# Papa_Soundie.net
KiCad netlist of a schematic drawn in EAGLE
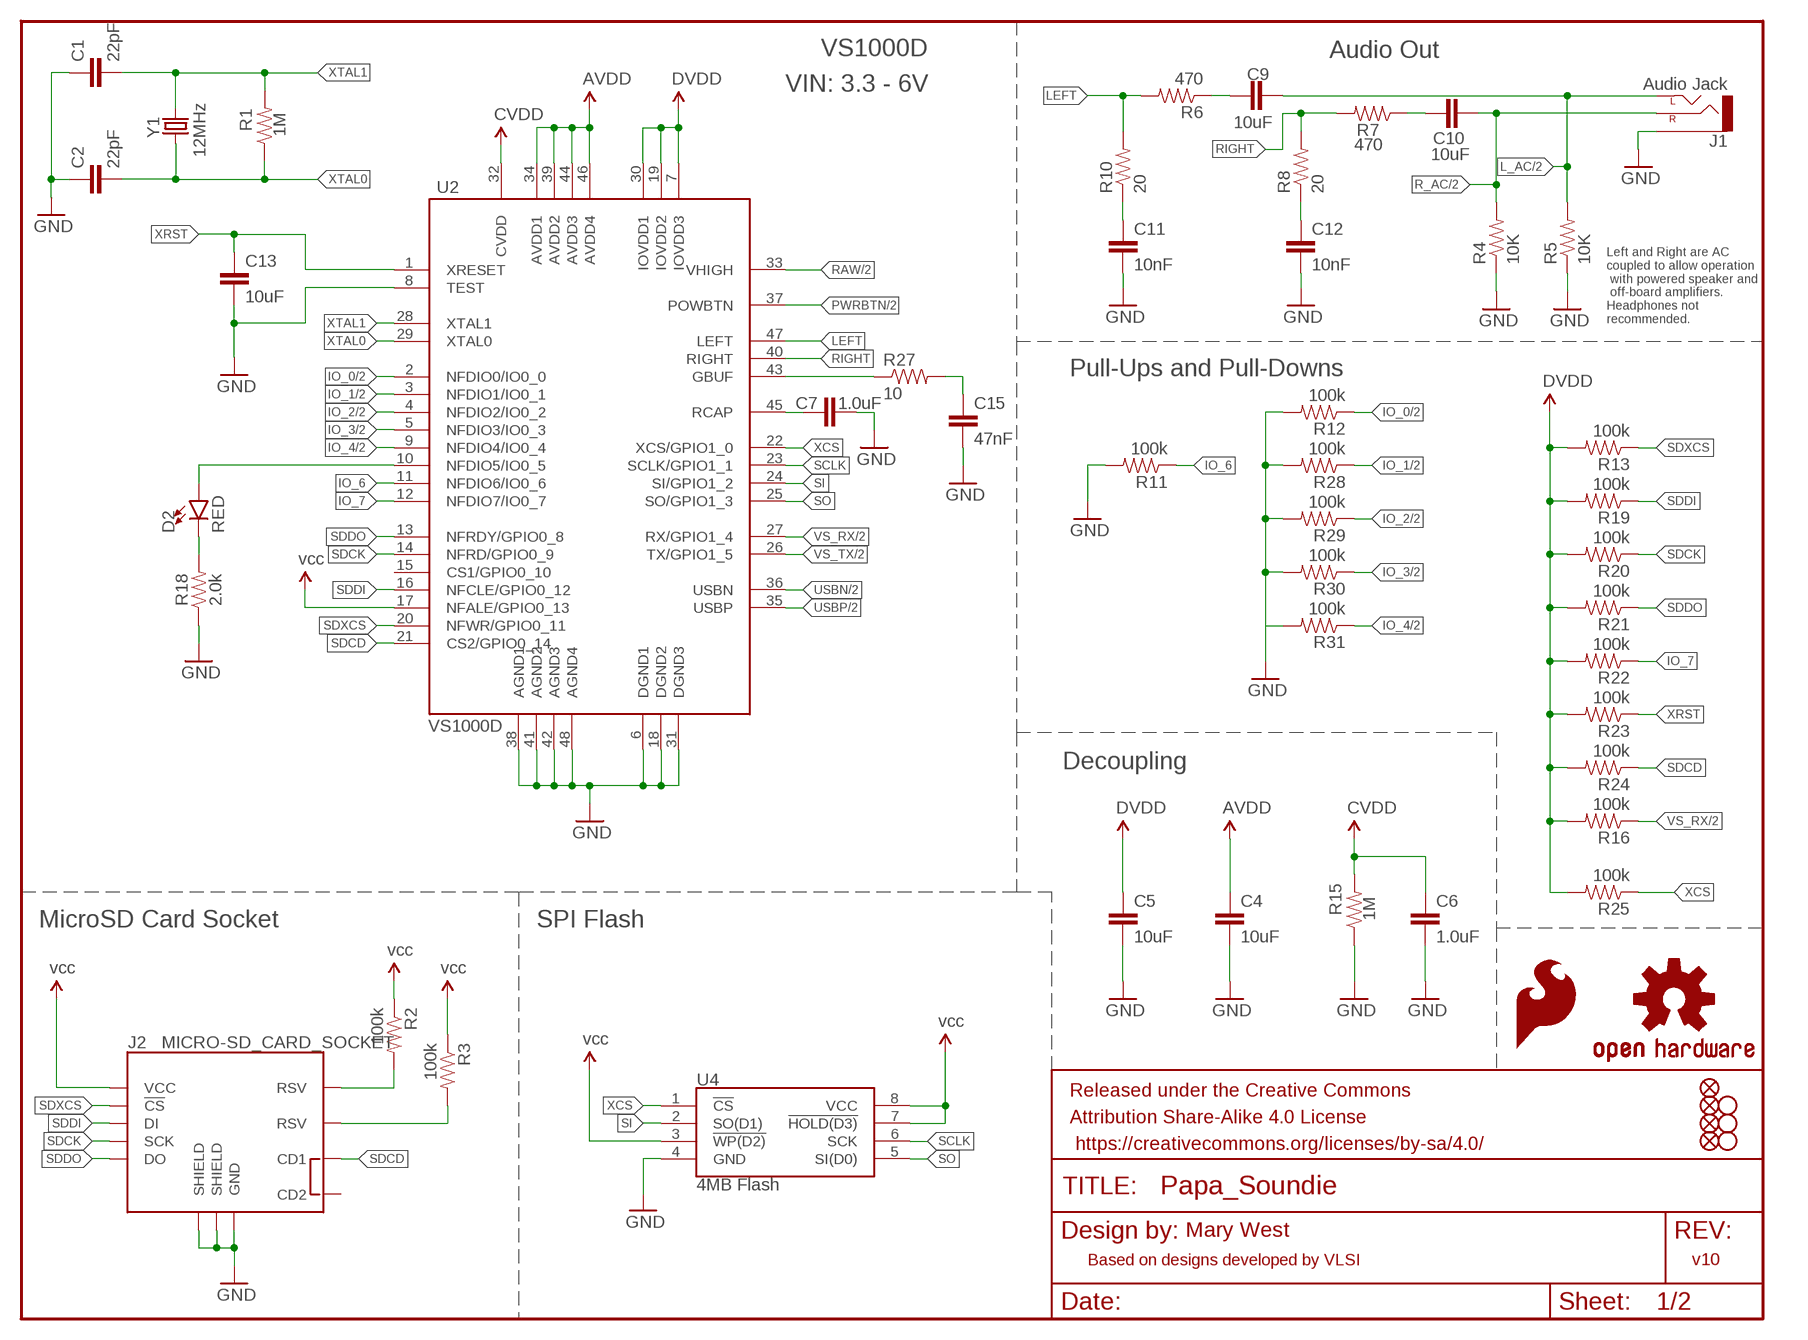
[diagram p0: schematic, sheet 1]
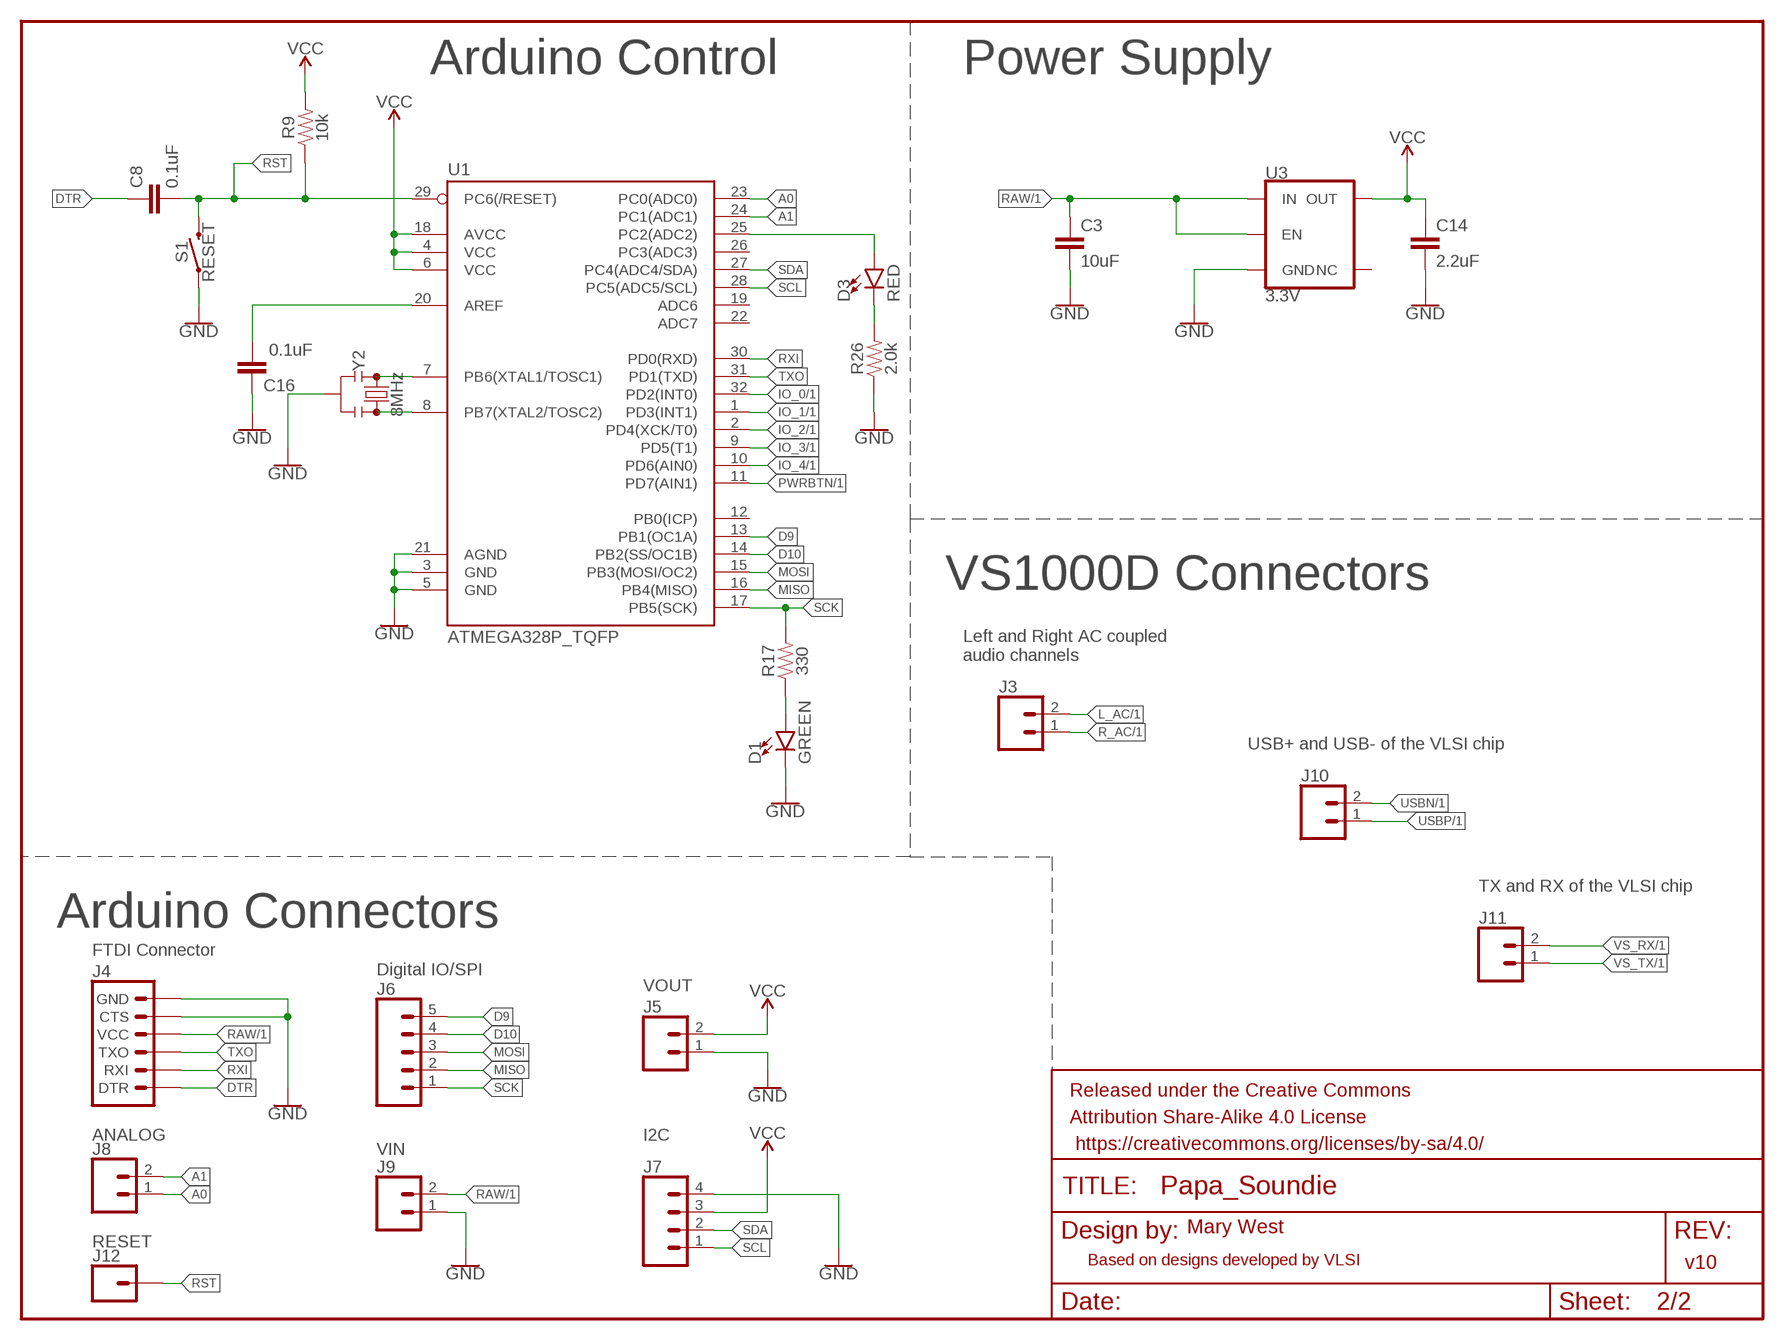
[diagram p1: schematic, sheet 2]

(export (version "E")
  (design (tool "Eeschema 10.0.6"))
  (components
    (comp (ref "C3")
      (value "10uF")
      (footprint "eagle-import:0603")
      (libsource (lib "eagle-import") (part "10UF-0603-6.3V-20%"))
    )
    (comp (ref "C8")
      (value "0.1uF")
      (footprint "eagle-import:0603")
      (libsource (lib "eagle-import") (part "0.1UF-0603-25V-(+80/-20%)"))
    )
    (comp (ref "C14")
      (value "2.2uF")
      (footprint "eagle-import:0603")
      (libsource (lib "eagle-import") (part "2.2UF-0603-10V-20%"))
    )
    (comp (ref "C16")
      (value "0.1uF")
      (footprint "eagle-import:0603")
      (libsource (lib "eagle-import") (part "0.1UF-0603-25V-(+80/-20%)"))
    )
    (comp (ref "D1")
      (value "GREEN")
      (footprint "eagle-import:LED-0603")
      (libsource (lib "eagle-import") (part "LED-GREEN0603"))
    )
    (comp (ref "D3")
      (value "RED")
      (footprint "eagle-import:LED-0603")
      (libsource (lib "eagle-import") (part "LED-RED0603"))
    )
    (comp (ref "FRAME2")
      (value "FRAME-LETTER")
      (footprint "eagle-import:CREATIVE_COMMONS")
      (libsource (lib "eagle-import") (part "FRAME-LETTER"))
    )
    (comp (ref "J3")
      (value "CONN_02")
      (footprint "eagle-import:1X02")
      (libsource (lib "eagle-import") (part "CONN_02"))
    )
    (comp (ref "J4")
      (value "6_PIN_SERIAL_TARGETSILK")
      (footprint "eagle-import:6_PIN_SERIAL_TARGET_SIDE_W_SILK")
      (libsource (lib "eagle-import") (part "6_PIN_SERIAL_TARGETSILK"))
    )
    (comp (ref "J5")
      (value "CONN_02")
      (footprint "eagle-import:1X02")
      (libsource (lib "eagle-import") (part "CONN_02"))
    )
    (comp (ref "J6")
      (value "CONN_05")
      (footprint "eagle-import:1X05")
      (libsource (lib "eagle-import") (part "CONN_05"))
    )
    (comp (ref "J7")
      (value "CONN_04")
      (footprint "eagle-import:1X04")
      (libsource (lib "eagle-import") (part "CONN_04"))
    )
    (comp (ref "J8")
      (value "CONN_02")
      (footprint "eagle-import:1X02")
      (libsource (lib "eagle-import") (part "CONN_02"))
    )
    (comp (ref "J9")
      (value "CONN_02")
      (footprint "eagle-import:1X02")
      (libsource (lib "eagle-import") (part "CONN_02"))
    )
    (comp (ref "J10")
      (value "CONN_02")
      (footprint "eagle-import:1X02")
      (libsource (lib "eagle-import") (part "CONN_02"))
    )
    (comp (ref "J11")
      (value "CONN_02")
      (footprint "eagle-import:1X02")
      (libsource (lib "eagle-import") (part "CONN_02"))
    )
    (comp (ref "J12")
      (value "CONN_01")
      (footprint "eagle-import:1X01")
      (libsource (lib "eagle-import") (part "CONN_01"))
    )
    (comp (ref "R9")
      (value "10k")
      (footprint "eagle-import:0603")
      (libsource (lib "eagle-import") (part "10KOHM-0603-1/10W-1%"))
    )
    (comp (ref "R17")
      (value "330")
      (footprint "eagle-import:0603")
      (libsource (lib "eagle-import") (part "330OHM-0603-1/10W-1%"))
    )
    (comp (ref "R26")
      (value "2.0k")
      (footprint "eagle-import:0603")
      (libsource (lib "eagle-import") (part "2.0KOHM-0603-1/10W-5%"))
    )
    (comp (ref "S1")
      (value "RESET")
      (footprint "eagle-import:TACTILE_SWITCH_SMD_5.2MM")
      (libsource (lib "eagle-import") (part "MOMENTARY-SWITCH-SPST-SMD-5.2MM"))
    )
    (comp (ref "U1")
      (value "ATMEGA328P_TQFP")
      (footprint "eagle-import:TQFP32-08")
      (libsource (lib "eagle-import") (part "ATMEGA328P_TQFP"))
    )
    (comp (ref "U3")
      (value "3.3V")
      (footprint "eagle-import:SOT23-5")
      (libsource (lib "eagle-import") (part "V_REG_AP2112K-3.3V"))
    )
    (comp (ref "Y2")
      (value "8MHz")
      (footprint "eagle-import:RESONATOR-SMD-3.2X1.3")
      (libsource (lib "eagle-import") (part "RESONATOR-8MHZSMD_3.2X1.3"))
    )
    (comp (ref "C1")
      (value "22pF")
      (footprint "eagle-import:0603-CAP")
      (libsource (lib "eagle-import") (part "22PF-50V-5%(0603)"))
    )
    (comp (ref "C2")
      (value "22pF")
      (footprint "eagle-import:0603-CAP")
      (libsource (lib "eagle-import") (part "22PF-50V-5%(0603)"))
    )
    (comp (ref "C4")
      (value "10uF")
      (footprint "eagle-import:0603")
      (libsource (lib "eagle-import") (part "10UF-0603-6.3V-20%"))
    )
    (comp (ref "C5")
      (value "10uF")
      (footprint "eagle-import:0603")
      (libsource (lib "eagle-import") (part "10UF-0603-6.3V-20%"))
    )
    (comp (ref "C6")
      (value "1.0uF")
      (footprint "eagle-import:0603-CAP")
      (libsource (lib "eagle-import") (part "1.0UF-16V-10%(0603)"))
    )
    (comp (ref "C7")
      (value "1.0uF")
      (footprint "eagle-import:0603-CAP")
      (libsource (lib "eagle-import") (part "1.0UF-16V-10%(0603)"))
    )
    (comp (ref "C9")
      (value "10uF")
      (footprint "eagle-import:0603-CAP")
      (libsource (lib "eagle-import") (part "10UF-6.3V-20%(0603)"))
    )
    (comp (ref "C10")
      (value "10uF")
      (footprint "eagle-import:0603-CAP")
      (libsource (lib "eagle-import") (part "10UF-6.3V-20%(0603)"))
    )
    (comp (ref "C11")
      (value "10nF")
      (footprint "eagle-import:0603-CAP")
      (libsource (lib "eagle-import") (part "10NF/10000PF-50V-10%(0603)"))
    )
    (comp (ref "C12")
      (value "10nF")
      (footprint "eagle-import:0603-CAP")
      (libsource (lib "eagle-import") (part "10NF/10000PF-50V-10%(0603)"))
    )
    (comp (ref "C13")
      (value "10uF")
      (footprint "eagle-import:0603-CAP")
      (libsource (lib "eagle-import") (part "10UF-6.3V-20%(0603)"))
    )
    (comp (ref "C15")
      (value "47nF")
      (footprint "eagle-import:0603-CAP")
      (libsource (lib "eagle-import") (part "47NF(0.047UF/47000PF)-25V-5%(0603)SMD"))
    )
    (comp (ref "D2")
      (value "RED")
      (footprint "eagle-import:LED-0603")
      (libsource (lib "eagle-import") (part "LED-RED0603"))
    )
    (comp (ref "FD1")
      (value "FIDUCIALUFIDUCIAL")
      (footprint "eagle-import:FIDUCIAL-MICRO")
      (libsource (lib "eagle-import") (part "FIDUCIALUFIDUCIAL"))
    )
    (comp (ref "FD2")
      (value "FIDUCIALUFIDUCIAL")
      (footprint "eagle-import:FIDUCIAL-MICRO")
      (libsource (lib "eagle-import") (part "FIDUCIALUFIDUCIAL"))
    )
    (comp (ref "FD3")
      (value "FIDUCIALUFIDUCIAL")
      (footprint "eagle-import:FIDUCIAL-MICRO")
      (libsource (lib "eagle-import") (part "FIDUCIALUFIDUCIAL"))
    )
    (comp (ref "FD4")
      (value "FIDUCIALUFIDUCIAL")
      (footprint "eagle-import:FIDUCIAL-MICRO")
      (libsource (lib "eagle-import") (part "FIDUCIALUFIDUCIAL"))
    )
    (comp (ref "FRAME1")
      (value "FRAME-LETTER")
      (footprint "eagle-import:CREATIVE_COMMONS")
      (libsource (lib "eagle-import") (part "FRAME-LETTER"))
    )
    (comp (ref "H1")
      (value "STAND-OFFTIGHT")
      (footprint "eagle-import:STAND-OFF-TIGHT")
      (libsource (lib "eagle-import") (part "STAND-OFFTIGHT"))
    )
    (comp (ref "H2")
      (value "STAND-OFFTIGHT")
      (footprint "eagle-import:STAND-OFF-TIGHT")
      (libsource (lib "eagle-import") (part "STAND-OFFTIGHT"))
    )
    (comp (ref "H3")
      (value "STAND-OFFTIGHT")
      (footprint "eagle-import:STAND-OFF-TIGHT")
      (libsource (lib "eagle-import") (part "STAND-OFFTIGHT"))
    )
    (comp (ref "J1")
      (value "Audio Jack")
      (footprint "eagle-import:AUDIO-JACK-3.5MM-SMD")
      (libsource (lib "eagle-import") (part "AUDIO-JACKSMD2"))
    )
    (comp (ref "J2")
      (value "MICRO-SD_CARD_SOCKET")
      (footprint "eagle-import:MICRO-SD-SOCKET")
      (libsource (lib "eagle-import") (part "MICRO-SD_CARD_SOCKET"))
    )
    (comp (ref "LOGO1")
      (value "OSHW-LOGOL")
      (footprint "eagle-import:OSHW-LOGO-L")
      (libsource (lib "eagle-import") (part "OSHW-LOGOL"))
    )
    (comp (ref "LOGO2")
      (value "SFE_LOGO_FLAME.2_INCH")
      (footprint "eagle-import:SFE_LOGO_FLAME_.2")
      (libsource (lib "eagle-import") (part "SFE_LOGO_FLAME.2_INCH"))
    )
    (comp (ref "R1")
      (value "1M")
      (footprint "eagle-import:0603-RES")
      (libsource (lib "eagle-import") (part "1MOHM-1/10W-1%(0603)"))
    )
    (comp (ref "R2")
      (value "100k")
      (footprint "eagle-import:0603-RES")
      (libsource (lib "eagle-import") (part "100KOHM-1/10W-1%(0603)"))
    )
    (comp (ref "R3")
      (value "100k")
      (footprint "eagle-import:0603-RES")
      (libsource (lib "eagle-import") (part "100KOHM-1/10W-1%(0603)"))
    )
    (comp (ref "R4")
      (value "10K")
      (footprint "eagle-import:0603-RES")
      (libsource (lib "eagle-import") (part "10KOHM-1/10W-1%(0603)0603"))
    )
    (comp (ref "R5")
      (value "10K")
      (footprint "eagle-import:0603-RES")
      (libsource (lib "eagle-import") (part "10KOHM-1/10W-1%(0603)0603"))
    )
    (comp (ref "R6")
      (value "470")
      (footprint "eagle-import:0603-RES")
      (libsource (lib "eagle-import") (part "470OHM1/10W1%(0603)"))
    )
    (comp (ref "R7")
      (value "470")
      (footprint "eagle-import:0603-RES")
      (libsource (lib "eagle-import") (part "470OHM1/10W1%(0603)"))
    )
    (comp (ref "R8")
      (value "20")
      (footprint "eagle-import:0603-RES")
      (libsource (lib "eagle-import") (part "20OHM1/10W1%(0603)SMD"))
    )
    (comp (ref "R10")
      (value "20")
      (footprint "eagle-import:0603-RES")
      (libsource (lib "eagle-import") (part "20OHM1/10W1%(0603)SMD"))
    )
    (comp (ref "R11")
      (value "100k")
      (footprint "eagle-import:0603-RES")
      (libsource (lib "eagle-import") (part "100KOHM-1/10W-1%(0603)"))
    )
    (comp (ref "R12")
      (value "100k")
      (footprint "eagle-import:0603-RES")
      (libsource (lib "eagle-import") (part "100KOHM-1/10W-1%(0603)"))
    )
    (comp (ref "R13")
      (value "100k")
      (footprint "eagle-import:0603-RES")
      (libsource (lib "eagle-import") (part "100KOHM-1/10W-1%(0603)"))
    )
    (comp (ref "R15")
      (value "1M")
      (footprint "eagle-import:0603-RES")
      (libsource (lib "eagle-import") (part "1MOHM-1/10W-1%(0603)"))
    )
    (comp (ref "R16")
      (value "100k")
      (footprint "eagle-import:0603-RES")
      (libsource (lib "eagle-import") (part "100KOHM-1/10W-1%(0603)"))
    )
    (comp (ref "R18")
      (value "2.0k")
      (footprint "eagle-import:0603")
      (libsource (lib "eagle-import") (part "2.0KOHM-0603-1/10W-5%"))
    )
    (comp (ref "R19")
      (value "100k")
      (footprint "eagle-import:0603-RES")
      (libsource (lib "eagle-import") (part "100KOHM-1/10W-1%(0603)"))
    )
    (comp (ref "R20")
      (value "100k")
      (footprint "eagle-import:0603-RES")
      (libsource (lib "eagle-import") (part "100KOHM-1/10W-1%(0603)"))
    )
    (comp (ref "R21")
      (value "100k")
      (footprint "eagle-import:0603-RES")
      (libsource (lib "eagle-import") (part "100KOHM-1/10W-1%(0603)"))
    )
    (comp (ref "R22")
      (value "100k")
      (footprint "eagle-import:0603-RES")
      (libsource (lib "eagle-import") (part "100KOHM-1/10W-1%(0603)"))
    )
    (comp (ref "R23")
      (value "100k")
      (footprint "eagle-import:0603-RES")
      (libsource (lib "eagle-import") (part "100KOHM-1/10W-1%(0603)"))
    )
    (comp (ref "R24")
      (value "100k")
      (footprint "eagle-import:0603-RES")
      (libsource (lib "eagle-import") (part "100KOHM-1/10W-1%(0603)"))
    )
    (comp (ref "R25")
      (value "100k")
      (footprint "eagle-import:0603-RES")
      (libsource (lib "eagle-import") (part "100KOHM-1/10W-1%(0603)"))
    )
    (comp (ref "R27")
      (value "10")
      (footprint "eagle-import:0603-RES")
      (libsource (lib "eagle-import") (part "10OHM-1/10W-5%0603SMD"))
    )
    (comp (ref "R28")
      (value "100k")
      (footprint "eagle-import:0603-RES")
      (libsource (lib "eagle-import") (part "100KOHM-1/10W-1%(0603)"))
    )
    (comp (ref "R29")
      (value "100k")
      (footprint "eagle-import:0603-RES")
      (libsource (lib "eagle-import") (part "100KOHM-1/10W-1%(0603)"))
    )
    (comp (ref "R30")
      (value "100k")
      (footprint "eagle-import:0603-RES")
      (libsource (lib "eagle-import") (part "100KOHM-1/10W-1%(0603)"))
    )
    (comp (ref "R31")
      (value "100k")
      (footprint "eagle-import:0603-RES")
      (libsource (lib "eagle-import") (part "100KOHM-1/10W-1%(0603)"))
    )
    (comp (ref "U2")
      (value "VS1000D")
      (footprint "eagle-import:LQFP-48")
      (fields (field (name "PROD_ID") "LPA-12743"))
      (libsource (lib "eagle-import") (part "VS1000"))
    )
    (comp (ref "U4")
      (value "4MB Flash")
      (footprint "eagle-import:SO08")
      (libsource (lib "eagle-import") (part "AT25SF041"))
    )
    (comp (ref "Y1")
      (value "12MHz")
      (footprint "eagle-import:CRYSTAL-SMD-5X3")
      (libsource (lib "eagle-import") (part "CRYSTALCRYSTAL-SMD-5X3-12MHZ"))
    )
  )
  (nets
    (net (code "1") (name "A0") (class "Default")
      (node (ref "J8") (pin "1") (pinfunction "1_1") (pintype "passive"))
      (node (ref "U1") (pin "23") (pinfunction "PC0(ADC0)_23") (pintype "bidirectional"))
    )
    (net (code "2") (name "A1") (class "Default")
      (node (ref "J8") (pin "2") (pinfunction "2_2") (pintype "passive"))
      (node (ref "U1") (pin "24") (pinfunction "PC1(ADC1)_24") (pintype "bidirectional"))
    )
    (net (code "3") (name "AVDD") (class "Default")
      (node (ref "C4") (pin "1") (pinfunction "1_1") (pintype "passive"))
      (node (ref "U2") (pin "34") (pinfunction "AVDD1_34") (pintype "bidirectional"))
      (node (ref "U2") (pin "39") (pinfunction "AVDD2_39") (pintype "bidirectional"))
      (node (ref "U2") (pin "44") (pinfunction "AVDD3_44") (pintype "bidirectional"))
      (node (ref "U2") (pin "46") (pinfunction "AVDD4_46") (pintype "bidirectional"))
    )
    (net (code "4") (name "CVDD") (class "Default")
      (node (ref "C6") (pin "1") (pinfunction "1_1") (pintype "passive"))
      (node (ref "R15") (pin "2") (pinfunction "2_2") (pintype "passive"))
      (node (ref "U2") (pin "32") (pinfunction "CVDD_32") (pintype "bidirectional"))
    )
    (net (code "5") (name "D9") (class "Default")
      (node (ref "J6") (pin "5") (pinfunction "5_5") (pintype "passive"))
      (node (ref "U1") (pin "13") (pinfunction "PB1(OC1A)_13") (pintype "bidirectional"))
    )
    (net (code "6") (name "D10") (class "Default")
      (node (ref "J6") (pin "4") (pinfunction "4_4") (pintype "passive"))
      (node (ref "U1") (pin "14") (pinfunction "PB2(SS/OC1B)_14") (pintype "bidirectional"))
    )
    (net (code "7") (name "DTR") (class "Default")
      (node (ref "C8") (pin "1") (pinfunction "1_1") (pintype "passive"))
      (node (ref "J4") (pin "P$1") (pinfunction "DTR_P$1") (pintype "passive"))
    )
    (net (code "8") (name "DVDD") (class "Default")
      (node (ref "C5") (pin "1") (pinfunction "1_1") (pintype "passive"))
      (node (ref "R13") (pin "2") (pinfunction "2_2") (pintype "passive"))
      (node (ref "R16") (pin "2") (pinfunction "2_2") (pintype "passive"))
      (node (ref "R19") (pin "2") (pinfunction "2_2") (pintype "passive"))
      (node (ref "R20") (pin "2") (pinfunction "2_2") (pintype "passive"))
      (node (ref "R21") (pin "2") (pinfunction "2_2") (pintype "passive"))
      (node (ref "R22") (pin "2") (pinfunction "2_2") (pintype "passive"))
      (node (ref "R23") (pin "2") (pinfunction "2_2") (pintype "passive"))
      (node (ref "R24") (pin "2") (pinfunction "2_2") (pintype "passive"))
      (node (ref "R25") (pin "2") (pinfunction "2_2") (pintype "passive"))
      (node (ref "U2") (pin "19") (pinfunction "IOVDD2_19") (pintype "bidirectional"))
      (node (ref "U2") (pin "30") (pinfunction "IOVDD1_30") (pintype "bidirectional"))
      (node (ref "U2") (pin "7") (pinfunction "IOVDD3_7") (pintype "bidirectional"))
    )
    (net (code "9") (name "GND") (class "Default")
      (node (ref "C1") (pin "1") (pinfunction "1_1") (pintype "passive"))
      (node (ref "C11") (pin "2") (pinfunction "2_2") (pintype "passive"))
      (node (ref "C12") (pin "2") (pinfunction "2_2") (pintype "passive"))
      (node (ref "C13") (pin "2") (pinfunction "2_2") (pintype "passive"))
      (node (ref "C14") (pin "2") (pinfunction "2_2") (pintype "passive"))
      (node (ref "C15") (pin "2") (pinfunction "2_2") (pintype "passive"))
      (node (ref "C16") (pin "1") (pinfunction "1_1") (pintype "passive"))
      (node (ref "C2") (pin "1") (pinfunction "1_1") (pintype "passive"))
      (node (ref "C3") (pin "2") (pinfunction "2_2") (pintype "passive"))
      (node (ref "C4") (pin "2") (pinfunction "2_2") (pintype "passive"))
      (node (ref "C5") (pin "2") (pinfunction "2_2") (pintype "passive"))
      (node (ref "C6") (pin "2") (pinfunction "2_2") (pintype "passive"))
      (node (ref "C7") (pin "2") (pinfunction "2_2") (pintype "passive"))
      (node (ref "D1") (pin "C") (pinfunction "C_C") (pintype "passive"))
      (node (ref "J1") (pin "SLEEVE") (pinfunction "SLEEVE_SLEEVE") (pintype "bidirectional"))
      (node (ref "J2") (pin "GND") (pinfunction "GND_GND") (pintype "bidirectional"))
      (node (ref "J2") (pin "GND1") (pinfunction "SHIELD_GND1") (pintype "bidirectional"))
      (node (ref "J2") (pin "GND3") (pinfunction "SHIELD_GND3") (pintype "bidirectional"))
      (node (ref "J4") (pin "P$5") (pinfunction "CTS_P$5") (pintype "passive"))
      (node (ref "J4") (pin "P$6") (pinfunction "GND_P$6") (pintype "passive"))
      (node (ref "J5") (pin "1") (pinfunction "1_1") (pintype "passive"))
      (node (ref "J7") (pin "4") (pinfunction "4_4") (pintype "passive"))
      (node (ref "J9") (pin "1") (pinfunction "1_1") (pintype "passive"))
      (node (ref "R11") (pin "2") (pinfunction "2_2") (pintype "passive"))
      (node (ref "R12") (pin "2") (pinfunction "2_2") (pintype "passive"))
      (node (ref "R15") (pin "1") (pinfunction "1_1") (pintype "passive"))
      (node (ref "R18") (pin "1") (pinfunction "1_1") (pintype "passive"))
      (node (ref "R26") (pin "1") (pinfunction "1_1") (pintype "passive"))
      (node (ref "R28") (pin "2") (pinfunction "2_2") (pintype "passive"))
      (node (ref "R29") (pin "2") (pinfunction "2_2") (pintype "passive"))
      (node (ref "R30") (pin "2") (pinfunction "2_2") (pintype "passive"))
      (node (ref "R31") (pin "2") (pinfunction "2_2") (pintype "passive"))
      (node (ref "R4") (pin "1") (pinfunction "1_1") (pintype "passive"))
      (node (ref "R5") (pin "1") (pinfunction "1_1") (pintype "passive"))
      (node (ref "S1") (pin "1") (pinfunction "1_1") (pintype "passive"))
      (node (ref "U1") (pin "21") (pinfunction "AGND_21") (pintype "bidirectional"))
      (node (ref "U1") (pin "3") (pinfunction "GND_3") (pintype "bidirectional"))
      (node (ref "U1") (pin "5") (pinfunction "GND_5") (pintype "bidirectional"))
      (node (ref "U2") (pin "18") (pinfunction "DGND2_18") (pintype "bidirectional"))
      (node (ref "U2") (pin "31") (pinfunction "DGND3_31") (pintype "bidirectional"))
      (node (ref "U2") (pin "38") (pinfunction "AGND1_38") (pintype "bidirectional"))
      (node (ref "U2") (pin "41") (pinfunction "AGND2_41") (pintype "bidirectional"))
      (node (ref "U2") (pin "42") (pinfunction "AGND3_42") (pintype "bidirectional"))
      (node (ref "U2") (pin "48") (pinfunction "AGND4_48") (pintype "bidirectional"))
      (node (ref "U2") (pin "6") (pinfunction "DGND1_6") (pintype "bidirectional"))
      (node (ref "U2") (pin "8") (pinfunction "TEST_8") (pintype "bidirectional"))
      (node (ref "U3") (pin "2") (pinfunction "GND_2") (pintype "input"))
      (node (ref "U4") (pin "4") (pinfunction "GND_4") (pintype "bidirectional"))
      (node (ref "Y2") (pin "2") (pinfunction "2_2") (pintype "passive"))
    )
    (net (code "10") (name "IO_0") (class "Default")
      (node (ref "R12") (pin "1") (pinfunction "1_1") (pintype "passive"))
      (node (ref "U1") (pin "32") (pinfunction "PD2(INT0)_32") (pintype "bidirectional"))
      (node (ref "U2") (pin "2") (pinfunction "NFDIO0/IO0_0_2") (pintype "bidirectional"))
    )
    (net (code "11") (name "IO_1") (class "Default")
      (node (ref "R28") (pin "1") (pinfunction "1_1") (pintype "passive"))
      (node (ref "U1") (pin "1") (pinfunction "PD3(INT1)_1") (pintype "bidirectional"))
      (node (ref "U2") (pin "3") (pinfunction "NFDIO1/IO0_1_3") (pintype "bidirectional"))
    )
    (net (code "12") (name "IO_2") (class "Default")
      (node (ref "R29") (pin "1") (pinfunction "1_1") (pintype "passive"))
      (node (ref "U1") (pin "2") (pinfunction "PD4(XCK/T0)_2") (pintype "bidirectional"))
      (node (ref "U2") (pin "4") (pinfunction "NFDIO2/IO0_2_4") (pintype "bidirectional"))
    )
    (net (code "13") (name "IO_3") (class "Default")
      (node (ref "R30") (pin "1") (pinfunction "1_1") (pintype "passive"))
      (node (ref "U1") (pin "9") (pinfunction "PD5(T1)_9") (pintype "bidirectional"))
      (node (ref "U2") (pin "5") (pinfunction "NFDIO3/IO0_3_5") (pintype "bidirectional"))
    )
    (net (code "14") (name "IO_4") (class "Default")
      (node (ref "R31") (pin "1") (pinfunction "1_1") (pintype "passive"))
      (node (ref "U1") (pin "10") (pinfunction "PD6(AIN0)_10") (pintype "bidirectional"))
      (node (ref "U2") (pin "9") (pinfunction "NFDIO4/IO0_4_9") (pintype "bidirectional"))
    )
    (net (code "15") (name "IO_6") (class "Default")
      (node (ref "R11") (pin "1") (pinfunction "1_1") (pintype "passive"))
      (node (ref "U2") (pin "11") (pinfunction "NFDIO6/IO0_6_11") (pintype "bidirectional"))
    )
    (net (code "16") (name "IO_7") (class "Default")
      (node (ref "R22") (pin "1") (pinfunction "1_1") (pintype "passive"))
      (node (ref "U2") (pin "12") (pinfunction "NFDIO7/IO0_7_12") (pintype "bidirectional"))
    )
    (net (code "17") (name "LEFT") (class "Default")
      (node (ref "R10") (pin "2") (pinfunction "2_2") (pintype "passive"))
      (node (ref "R6") (pin "2") (pinfunction "2_2") (pintype "passive"))
      (node (ref "U2") (pin "47") (pinfunction "LEFT_47") (pintype "bidirectional"))
    )
    (net (code "18") (name "L_AC") (class "Default")
      (node (ref "C9") (pin "2") (pinfunction "2_2") (pintype "passive"))
      (node (ref "J1") (pin "TIP") (pinfunction "LEFT_TIP") (pintype "bidirectional"))
      (node (ref "J3") (pin "2") (pinfunction "2_2") (pintype "passive"))
      (node (ref "R5") (pin "2") (pinfunction "2_2") (pintype "passive"))
    )
    (net (code "19") (name "MISO") (class "Default")
      (node (ref "J6") (pin "2") (pinfunction "2_2") (pintype "passive"))
      (node (ref "U1") (pin "16") (pinfunction "PB4(MISO)_16") (pintype "bidirectional"))
    )
    (net (code "20") (name "MOSI") (class "Default")
      (node (ref "J6") (pin "3") (pinfunction "3_3") (pintype "passive"))
      (node (ref "U1") (pin "15") (pinfunction "PB3(MOSI/OC2)_15") (pintype "bidirectional"))
    )
    (net (code "21") (name "Net-(C9-Pad1)") (class "Default")
      (node (ref "C9") (pin "1") (pinfunction "1_1") (pintype "passive"))
      (node (ref "R6") (pin "1") (pinfunction "1_1") (pintype "passive"))
    )
    (net (code "22") (name "Net-(C10-Pad1)") (class "Default")
      (node (ref "C10") (pin "1") (pinfunction "1_1") (pintype "passive"))
      (node (ref "R7") (pin "1") (pinfunction "1_1") (pintype "passive"))
    )
    (net (code "23") (name "Net-(C11-Pad1)") (class "Default")
      (node (ref "C11") (pin "1") (pinfunction "1_1") (pintype "passive"))
      (node (ref "R10") (pin "1") (pinfunction "1_1") (pintype "passive"))
    )
    (net (code "24") (name "Net-(C12-Pad1)") (class "Default")
      (node (ref "C12") (pin "1") (pinfunction "1_1") (pintype "passive"))
      (node (ref "R8") (pin "1") (pinfunction "1_1") (pintype "passive"))
    )
    (net (code "25") (name "Net-(C15-Pad1)") (class "Default")
      (node (ref "C15") (pin "1") (pinfunction "1_1") (pintype "passive"))
      (node (ref "R27") (pin "2") (pinfunction "2_2") (pintype "passive"))
    )
    (net (code "26") (name "Net-(D1-PadA)") (class "Default")
      (node (ref "D1") (pin "A") (pinfunction "A_A") (pintype "passive"))
      (node (ref "R17") (pin "1") (pinfunction "1_1") (pintype "passive"))
    )
    (net (code "27") (name "Net-(D2-PadC)") (class "Default")
      (node (ref "D2") (pin "C") (pinfunction "C_C") (pintype "passive"))
      (node (ref "R18") (pin "2") (pinfunction "2_2") (pintype "passive"))
    )
    (net (code "28") (name "Net-(D3-PadC)") (class "Default")
      (node (ref "D3") (pin "C") (pinfunction "C_C") (pintype "passive"))
      (node (ref "R26") (pin "2") (pinfunction "2_2") (pintype "passive"))
    )
    (net (code "29") (name "Net-(J2-RSV-PadRSV1)") (class "Default")
      (node (ref "J2") (pin "RSV1") (pinfunction "RSV_RSV1") (pintype "bidirectional"))
      (node (ref "R2") (pin "2") (pinfunction "2_2") (pintype "passive"))
    )
    (net (code "30") (name "Net-(J2-RSV-PadRSV2)") (class "Default")
      (node (ref "J2") (pin "RSV2") (pinfunction "RSV_RSV2") (pintype "bidirectional"))
      (node (ref "R3") (pin "2") (pinfunction "2_2") (pintype "passive"))
    )
    (net (code "31") (name "Net-(U1-AREF)") (class "Default")
      (node (ref "C16") (pin "2") (pinfunction "2_2") (pintype "passive"))
      (node (ref "U1") (pin "20") (pinfunction "AREF_20") (pintype "bidirectional"))
    )
    (net (code "32") (name "Net-(U1-PB6(XTAL1{slash}TOSC1))") (class "Default")
      (node (ref "U1") (pin "7") (pinfunction "PB6(XTAL1/TOSC1)_7") (pintype "bidirectional"))
      (node (ref "Y2") (pin "1") (pinfunction "1_1") (pintype "passive"))
    )
    (net (code "33") (name "Net-(U1-PB7(XTAL2{slash}TOSC2))") (class "Default")
      (node (ref "U1") (pin "8") (pinfunction "PB7(XTAL2/TOSC2)_8") (pintype "bidirectional"))
      (node (ref "Y2") (pin "3") (pinfunction "3_3") (pintype "passive"))
    )
    (net (code "34") (name "Net-(U1-PC2(ADC2))") (class "Default")
      (node (ref "D3") (pin "A") (pinfunction "A_A") (pintype "passive"))
      (node (ref "U1") (pin "25") (pinfunction "PC2(ADC2)_25") (pintype "bidirectional"))
    )
    (net (code "35") (name "Net-(U2-GBUF)") (class "Default")
      (node (ref "R27") (pin "1") (pinfunction "1_1") (pintype "passive"))
      (node (ref "U2") (pin "43") (pinfunction "GBUF_43") (pintype "bidirectional"))
    )
    (net (code "36") (name "Net-(U2-NFDIO5{slash}IO0_5)") (class "Default")
      (node (ref "D2") (pin "A") (pinfunction "A_A") (pintype "passive"))
      (node (ref "U2") (pin "10") (pinfunction "NFDIO5/IO0_5_10") (pintype "bidirectional"))
    )
    (net (code "37") (name "Net-(U2-RCAP)") (class "Default")
      (node (ref "C7") (pin "1") (pinfunction "1_1") (pintype "passive"))
      (node (ref "U2") (pin "45") (pinfunction "RCAP_45") (pintype "bidirectional"))
    )
    (net (code "38") (name "PWRBTN") (class "Default")
      (node (ref "U1") (pin "11") (pinfunction "PD7(AIN1)_11") (pintype "bidirectional"))
      (node (ref "U2") (pin "37") (pinfunction "POWBTN_37") (pintype "bidirectional"))
    )
    (net (code "39") (name "RAW") (class "Default")
      (node (ref "C3") (pin "1") (pinfunction "1_1") (pintype "passive"))
      (node (ref "J4") (pin "P$4") (pinfunction "VCC_P$4") (pintype "passive"))
      (node (ref "J9") (pin "2") (pinfunction "2_2") (pintype "passive"))
      (node (ref "U2") (pin "33") (pinfunction "VHIGH_33") (pintype "bidirectional"))
      (node (ref "U3") (pin "1") (pinfunction "IN_1") (pintype "input"))
      (node (ref "U3") (pin "3") (pinfunction "EN_3") (pintype "input"))
    )
    (net (code "40") (name "RIGHT") (class "Default")
      (node (ref "R7") (pin "2") (pinfunction "2_2") (pintype "passive"))
      (node (ref "R8") (pin "2") (pinfunction "2_2") (pintype "passive"))
      (node (ref "U2") (pin "40") (pinfunction "RIGHT_40") (pintype "bidirectional"))
    )
    (net (code "41") (name "RST") (class "Default")
      (node (ref "C8") (pin "2") (pinfunction "2_2") (pintype "passive"))
      (node (ref "J12") (pin "1") (pinfunction "1_1") (pintype "passive"))
      (node (ref "R9") (pin "1") (pinfunction "1_1") (pintype "passive"))
      (node (ref "S1") (pin "3") (pinfunction "2_3") (pintype "passive"))
      (node (ref "U1") (pin "29") (pinfunction "PC6(/RESET)_29") (pintype "bidirectional"))
    )
    (net (code "42") (name "RXI") (class "Default")
      (node (ref "J4") (pin "P$3") (pinfunction "RXI_P$3") (pintype "passive"))
      (node (ref "U1") (pin "30") (pinfunction "PD0(RXD)_30") (pintype "bidirectional"))
    )
    (net (code "43") (name "R_AC") (class "Default")
      (node (ref "C10") (pin "2") (pinfunction "2_2") (pintype "passive"))
      (node (ref "J1") (pin "RING") (pinfunction "RIGHT_RING") (pintype "bidirectional"))
      (node (ref "J3") (pin "1") (pinfunction "1_1") (pintype "passive"))
      (node (ref "R4") (pin "2") (pinfunction "2_2") (pintype "passive"))
    )
    (net (code "44") (name "SCK") (class "Default")
      (node (ref "J6") (pin "1") (pinfunction "1_1") (pintype "passive"))
      (node (ref "R17") (pin "2") (pinfunction "2_2") (pintype "passive"))
      (node (ref "U1") (pin "17") (pinfunction "PB5(SCK)_17") (pintype "bidirectional"))
    )
    (net (code "45") (name "SCL") (class "Default")
      (node (ref "J7") (pin "1") (pinfunction "1_1") (pintype "passive"))
      (node (ref "U1") (pin "28") (pinfunction "PC5(ADC5/SCL)_28") (pintype "bidirectional"))
    )
    (net (code "46") (name "SCLK") (class "Default")
      (node (ref "U2") (pin "23") (pinfunction "SCLK/GPIO1_1_23") (pintype "bidirectional"))
      (node (ref "U4") (pin "6") (pinfunction "SCK_6") (pintype "bidirectional"))
    )
    (net (code "47") (name "SDA") (class "Default")
      (node (ref "J7") (pin "2") (pinfunction "2_2") (pintype "passive"))
      (node (ref "U1") (pin "27") (pinfunction "PC4(ADC4/SDA)_27") (pintype "bidirectional"))
    )
    (net (code "48") (name "SDCD") (class "Default")
      (node (ref "J2") (pin "CD1") (pinfunction "CD1_CD1") (pintype "bidirectional"))
      (node (ref "R24") (pin "1") (pinfunction "1_1") (pintype "passive"))
      (node (ref "U2") (pin "21") (pinfunction "CS2/GPIO0_14_21") (pintype "bidirectional"))
    )
    (net (code "49") (name "SDCK") (class "Default")
      (node (ref "J2") (pin "SCLK") (pinfunction "SCK_SCLK") (pintype "bidirectional"))
      (node (ref "R20") (pin "1") (pinfunction "1_1") (pintype "passive"))
      (node (ref "U2") (pin "14") (pinfunction "NFRD/GPIO0_9_14") (pintype "bidirectional"))
    )
    (net (code "50") (name "SDDI") (class "Default")
      (node (ref "J2") (pin "DI") (pinfunction "DI_DI") (pintype "bidirectional"))
      (node (ref "R19") (pin "1") (pinfunction "1_1") (pintype "passive"))
      (node (ref "U2") (pin "16") (pinfunction "NFCLE/GPIO0_12_16") (pintype "bidirectional"))
    )
    (net (code "51") (name "SDDO") (class "Default")
      (node (ref "J2") (pin "DO") (pinfunction "DO_DO") (pintype "bidirectional"))
      (node (ref "R21") (pin "1") (pinfunction "1_1") (pintype "passive"))
      (node (ref "U2") (pin "13") (pinfunction "NFRDY/GPIO0_8_13") (pintype "bidirectional"))
    )
    (net (code "52") (name "SDXCS") (class "Default")
      (node (ref "J2") (pin "CS") (pinfunction "~{CS}_CS") (pintype "bidirectional"))
      (node (ref "R13") (pin "1") (pinfunction "1_1") (pintype "passive"))
      (node (ref "U2") (pin "20") (pinfunction "NFWR/GPIO0_11_20") (pintype "bidirectional"))
    )
    (net (code "53") (name "SI") (class "Default")
      (node (ref "U2") (pin "24") (pinfunction "SI/GPIO1_2_24") (pintype "bidirectional"))
      (node (ref "U4") (pin "2") (pinfunction "SO(D1)_2") (pintype "bidirectional"))
    )
    (net (code "54") (name "SO") (class "Default")
      (node (ref "U2") (pin "25") (pinfunction "SO/GPIO1_3_25") (pintype "bidirectional"))
      (node (ref "U4") (pin "5") (pinfunction "SI(D0)_5") (pintype "bidirectional"))
    )
    (net (code "55") (name "TXO") (class "Default")
      (node (ref "J4") (pin "P$2") (pinfunction "TXO_P$2") (pintype "passive"))
      (node (ref "U1") (pin "31") (pinfunction "PD1(TXD)_31") (pintype "bidirectional"))
    )
    (net (code "56") (name "USBN") (class "Default")
      (node (ref "J10") (pin "2") (pinfunction "2_2") (pintype "passive"))
      (node (ref "U2") (pin "36") (pinfunction "USBN_36") (pintype "bidirectional"))
    )
    (net (code "57") (name "USBP") (class "Default")
      (node (ref "J10") (pin "1") (pinfunction "1_1") (pintype "passive"))
      (node (ref "U2") (pin "35") (pinfunction "USBP_35") (pintype "bidirectional"))
    )
    (net (code "58") (name "VCC") (class "Default")
      (node (ref "C14") (pin "1") (pinfunction "1_1") (pintype "passive"))
      (node (ref "J2") (pin "VCC") (pinfunction "VCC_VCC") (pintype "bidirectional"))
      (node (ref "J5") (pin "2") (pinfunction "2_2") (pintype "passive"))
      (node (ref "J7") (pin "3") (pinfunction "3_3") (pintype "passive"))
      (node (ref "R2") (pin "1") (pinfunction "1_1") (pintype "passive"))
      (node (ref "R3") (pin "1") (pinfunction "1_1") (pintype "passive"))
      (node (ref "R9") (pin "2") (pinfunction "2_2") (pintype "passive"))
      (node (ref "U1") (pin "18") (pinfunction "AVCC_18") (pintype "bidirectional"))
      (node (ref "U1") (pin "4") (pinfunction "VCC_4") (pintype "bidirectional"))
      (node (ref "U1") (pin "6") (pinfunction "VCC_6") (pintype "bidirectional"))
      (node (ref "U2") (pin "17") (pinfunction "NFALE/GPIO0_13_17") (pintype "bidirectional"))
      (node (ref "U3") (pin "5") (pinfunction "OUT_5") (pintype "passive"))
      (node (ref "U4") (pin "3") (pinfunction "~{WP(D2})_3") (pintype "bidirectional"))
      (node (ref "U4") (pin "7") (pinfunction "~{HOLD(D3})_7") (pintype "bidirectional"))
      (node (ref "U4") (pin "8") (pinfunction "VCC_8") (pintype "bidirectional"))
    )
    (net (code "59") (name "VS_RX") (class "Default")
      (node (ref "J11") (pin "2") (pinfunction "2_2") (pintype "passive"))
      (node (ref "R16") (pin "1") (pinfunction "1_1") (pintype "passive"))
      (node (ref "U2") (pin "27") (pinfunction "RX/GPIO1_4_27") (pintype "bidirectional"))
    )
    (net (code "60") (name "VS_TX") (class "Default")
      (node (ref "J11") (pin "1") (pinfunction "1_1") (pintype "passive"))
      (node (ref "U2") (pin "26") (pinfunction "TX/GPIO1_5_26") (pintype "bidirectional"))
    )
    (net (code "61") (name "XCS") (class "Default")
      (node (ref "R25") (pin "1") (pinfunction "1_1") (pintype "passive"))
      (node (ref "U2") (pin "22") (pinfunction "XCS/GPIO1_0_22") (pintype "bidirectional"))
      (node (ref "U4") (pin "1") (pinfunction "~{CS}_1") (pintype "bidirectional"))
    )
    (net (code "62") (name "XRST") (class "Default")
      (node (ref "C13") (pin "1") (pinfunction "1_1") (pintype "passive"))
      (node (ref "R23") (pin "1") (pinfunction "1_1") (pintype "passive"))
      (node (ref "U2") (pin "1") (pinfunction "XRESET_1") (pintype "bidirectional"))
    )
    (net (code "63") (name "XTAL0") (class "Default")
      (node (ref "C2") (pin "2") (pinfunction "2_2") (pintype "passive"))
      (node (ref "R1") (pin "1") (pinfunction "1_1") (pintype "passive"))
      (node (ref "U2") (pin "29") (pinfunction "XTAL0_29") (pintype "bidirectional"))
      (node (ref "Y1") (pin "1") (pinfunction "1_1") (pintype "passive"))
    )
    (net (code "64") (name "XTAL1") (class "Default")
      (node (ref "C1") (pin "2") (pinfunction "2_2") (pintype "passive"))
      (node (ref "R1") (pin "2") (pinfunction "2_2") (pintype "passive"))
      (node (ref "U2") (pin "28") (pinfunction "XTAL1_28") (pintype "bidirectional"))
      (node (ref "Y1") (pin "3") (pinfunction "2_3") (pintype "passive"))
    )
    (net (code "65") (name "unconnected-(J2-PadCD2)") (class "Default")
      (node (ref "J2") (pin "CD2") (pinfunction "CD2_CD2") (pintype "bidirectional"))
    )
    (net (code "66") (name "unconnected-(U1-ADC6-Pad19)") (class "Default")
      (node (ref "U1") (pin "19") (pinfunction "ADC6_19") (pintype "bidirectional"))
    )
    (net (code "67") (name "unconnected-(U1-ADC7-Pad22)") (class "Default")
      (node (ref "U1") (pin "22") (pinfunction "ADC7_22") (pintype "bidirectional"))
    )
    (net (code "68") (name "unconnected-(U1-PB0(ICP)-Pad12)") (class "Default")
      (node (ref "U1") (pin "12") (pinfunction "PB0(ICP)_12") (pintype "bidirectional"))
    )
    (net (code "69") (name "unconnected-(U1-PC3(ADC3)-Pad26)") (class "Default")
      (node (ref "U1") (pin "26") (pinfunction "PC3(ADC3)_26") (pintype "bidirectional"))
    )
    (net (code "70") (name "unconnected-(U2-CS1{slash}GPIO0_10-Pad15)") (class "Default")
      (node (ref "U2") (pin "15") (pinfunction "CS1/GPIO0_10_15") (pintype "bidirectional"))
    )
    (net (code "71") (name "unconnected-(U3-NC-Pad4)") (class "Default")
      (node (ref "U3") (pin "4") (pinfunction "NC_4") (pintype "no_connect"))
    )
  )
)
